# AIM65_FRAM.net
KiCad netlist of a schematic drawn in EAGLE
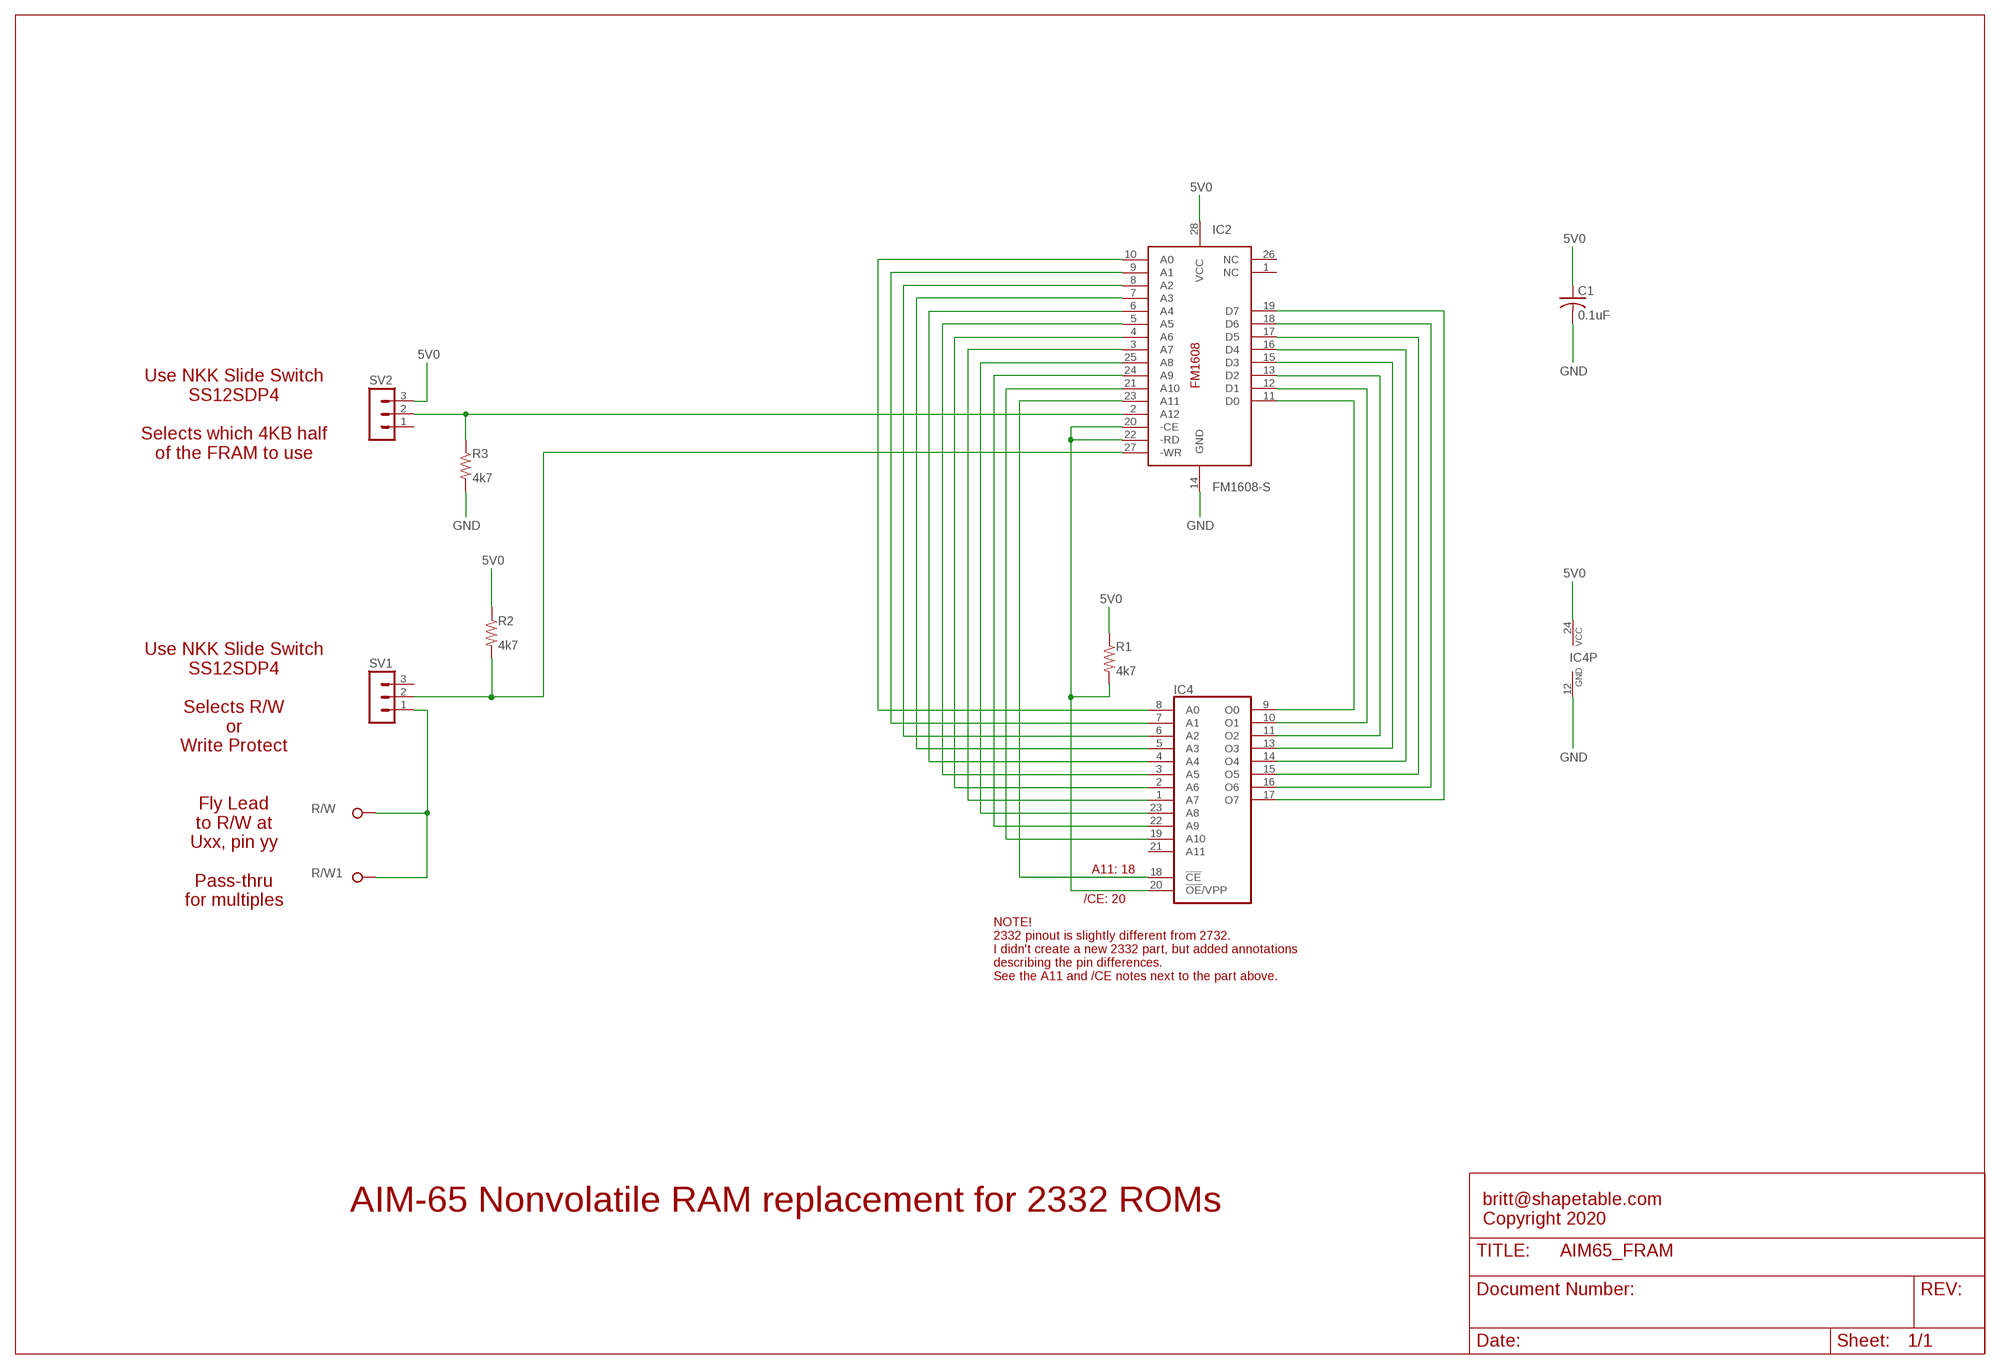
[diagram p0: schematic, sheet 1]

(export (version "E")
  (design (tool "Eeschema 10.0.6"))
  (components
    (comp (ref "C1")
      (value "0.1uF")
      (footprint "eagle-import:C0603K")
      (libsource (lib "eagle-import") (part "C-USC0603K"))
    )
    (comp (ref "IC2")
      (value "FM1608-S")
      (footprint "eagle-import:SO-28W")
      (libsource (lib "eagle-import") (part "FM1608-S"))
    )
    (comp (ref "IC4")
      (value "2732")
      (footprint "eagle-import:DIL24")
      (libsource (lib "eagle-import") (part "2732"))
    )
    (comp (ref "R/W")
      (value "JOE-TP-BIG")
      (footprint "eagle-import:JOE-TP-PKG-BIG")
      (libsource (lib "eagle-import") (part "JOE-TP-BIG"))
    )
    (comp (ref "R/W1")
      (value "JOE-TP-BIG")
      (footprint "eagle-import:JOE-TP-PKG-BIG")
      (libsource (lib "eagle-import") (part "JOE-TP-BIG"))
    )
    (comp (ref "R1")
      (value "4k7")
      (footprint "eagle-import:R0603")
      (libsource (lib "eagle-import") (part "R-US_R0603"))
    )
    (comp (ref "R2")
      (value "4k7")
      (footprint "eagle-import:R0603")
      (libsource (lib "eagle-import") (part "R-US_R0603"))
    )
    (comp (ref "R3")
      (value "4k7")
      (footprint "eagle-import:R0603")
      (libsource (lib "eagle-import") (part "R-US_R0603"))
    )
    (comp (ref "SV1")
      (value "MA03-1")
      (footprint "eagle-import:MA03-1")
      (libsource (lib "eagle-import") (part "MA03-1"))
    )
    (comp (ref "SV2")
      (value "MA03-1")
      (footprint "eagle-import:MA03-1")
      (libsource (lib "eagle-import") (part "MA03-1"))
    )
  )
  (nets
    (net (code "1") (name "/5V0") (class "Default")
      (node (ref "C1") (pin "1") (pinfunction "1_1") (pintype "passive"))
      (node (ref "IC2") (pin "28") (pinfunction "VCC_28") (pintype "power_in"))
      (node (ref "IC4") (pin "24") (pinfunction "VCC_24") (pintype "power_in"))
      (node (ref "R1") (pin "1") (pinfunction "1_1") (pintype "passive"))
      (node (ref "R2") (pin "1") (pinfunction "1_1") (pintype "passive"))
      (node (ref "SV2") (pin "3") (pinfunction "3_3") (pintype "passive"))
    )
    (net (code "2") (name "/GND") (class "Default")
      (node (ref "C1") (pin "2") (pinfunction "2_2") (pintype "passive"))
      (node (ref "IC2") (pin "14") (pinfunction "GND_14") (pintype "power_in"))
      (node (ref "IC4") (pin "12") (pinfunction "GND_12") (pintype "power_in"))
      (node (ref "R3") (pin "2") (pinfunction "2_2") (pintype "passive"))
    )
    (net (code "3") (name "Net-(IC2--CE)") (class "Default")
      (node (ref "IC2") (pin "20") (pinfunction "-CE_20") (pintype "input"))
      (node (ref "IC2") (pin "22") (pinfunction "-RD_22") (pintype "input"))
      (node (ref "IC4") (pin "20") (pinfunction "~{OE}/VPP_20") (pintype "input"))
      (node (ref "R1") (pin "2") (pinfunction "2_2") (pintype "passive"))
    )
    (net (code "4") (name "Net-(IC2--WR)") (class "Default")
      (node (ref "IC2") (pin "27") (pinfunction "-WR_27") (pintype "input"))
      (node (ref "R2") (pin "2") (pinfunction "2_2") (pintype "passive"))
      (node (ref "SV1") (pin "2") (pinfunction "2_2") (pintype "passive"))
    )
    (net (code "5") (name "Net-(IC2-A0)") (class "Default")
      (node (ref "IC2") (pin "10") (pinfunction "A0_10") (pintype "input"))
      (node (ref "IC4") (pin "8") (pinfunction "A0_8") (pintype "input"))
    )
    (net (code "6") (name "Net-(IC2-A1)") (class "Default")
      (node (ref "IC2") (pin "9") (pinfunction "A1_9") (pintype "input"))
      (node (ref "IC4") (pin "7") (pinfunction "A1_7") (pintype "input"))
    )
    (net (code "7") (name "Net-(IC2-A2)") (class "Default")
      (node (ref "IC2") (pin "8") (pinfunction "A2_8") (pintype "input"))
      (node (ref "IC4") (pin "6") (pinfunction "A2_6") (pintype "input"))
    )
    (net (code "8") (name "Net-(IC2-A3)") (class "Default")
      (node (ref "IC2") (pin "7") (pinfunction "A3_7") (pintype "input"))
      (node (ref "IC4") (pin "5") (pinfunction "A3_5") (pintype "input"))
    )
    (net (code "9") (name "Net-(IC2-A4)") (class "Default")
      (node (ref "IC2") (pin "6") (pinfunction "A4_6") (pintype "input"))
      (node (ref "IC4") (pin "4") (pinfunction "A4_4") (pintype "input"))
    )
    (net (code "10") (name "Net-(IC2-A5)") (class "Default")
      (node (ref "IC2") (pin "5") (pinfunction "A5_5") (pintype "input"))
      (node (ref "IC4") (pin "3") (pinfunction "A5_3") (pintype "input"))
    )
    (net (code "11") (name "Net-(IC2-A6)") (class "Default")
      (node (ref "IC2") (pin "4") (pinfunction "A6_4") (pintype "input"))
      (node (ref "IC4") (pin "2") (pinfunction "A6_2") (pintype "input"))
    )
    (net (code "12") (name "Net-(IC2-A7)") (class "Default")
      (node (ref "IC2") (pin "3") (pinfunction "A7_3") (pintype "input"))
      (node (ref "IC4") (pin "1") (pinfunction "A7_1") (pintype "input"))
    )
    (net (code "13") (name "Net-(IC2-A8)") (class "Default")
      (node (ref "IC2") (pin "25") (pinfunction "A8_25") (pintype "input"))
      (node (ref "IC4") (pin "23") (pinfunction "A8_23") (pintype "input"))
    )
    (net (code "14") (name "Net-(IC2-A9)") (class "Default")
      (node (ref "IC2") (pin "24") (pinfunction "A9_24") (pintype "input"))
      (node (ref "IC4") (pin "22") (pinfunction "A9_22") (pintype "input"))
    )
    (net (code "15") (name "Net-(IC2-A10)") (class "Default")
      (node (ref "IC2") (pin "21") (pinfunction "A10_21") (pintype "input"))
      (node (ref "IC4") (pin "19") (pinfunction "A10_19") (pintype "input"))
    )
    (net (code "16") (name "Net-(IC2-A11)") (class "Default")
      (node (ref "IC2") (pin "23") (pinfunction "A11_23") (pintype "input"))
      (node (ref "IC4") (pin "18") (pinfunction "~{CE}_18") (pintype "input"))
    )
    (net (code "17") (name "Net-(IC2-A12)") (class "Default")
      (node (ref "IC2") (pin "2") (pinfunction "A12_2") (pintype "input"))
      (node (ref "R3") (pin "1") (pinfunction "1_1") (pintype "passive"))
      (node (ref "SV2") (pin "2") (pinfunction "2_2") (pintype "passive"))
    )
    (net (code "18") (name "Net-(IC2-D0)") (class "Default")
      (node (ref "IC2") (pin "11") (pinfunction "D0_11") (pintype "bidirectional"))
      (node (ref "IC4") (pin "9") (pinfunction "O0_9") (pintype "tri_state"))
    )
    (net (code "19") (name "Net-(IC2-D1)") (class "Default")
      (node (ref "IC2") (pin "12") (pinfunction "D1_12") (pintype "bidirectional"))
      (node (ref "IC4") (pin "10") (pinfunction "O1_10") (pintype "tri_state"))
    )
    (net (code "20") (name "Net-(IC2-D2)") (class "Default")
      (node (ref "IC2") (pin "13") (pinfunction "D2_13") (pintype "bidirectional"))
      (node (ref "IC4") (pin "11") (pinfunction "O2_11") (pintype "tri_state"))
    )
    (net (code "21") (name "Net-(IC2-D3)") (class "Default")
      (node (ref "IC2") (pin "15") (pinfunction "D3_15") (pintype "bidirectional"))
      (node (ref "IC4") (pin "13") (pinfunction "O3_13") (pintype "tri_state"))
    )
    (net (code "22") (name "Net-(IC2-D4)") (class "Default")
      (node (ref "IC2") (pin "16") (pinfunction "D4_16") (pintype "bidirectional"))
      (node (ref "IC4") (pin "14") (pinfunction "O4_14") (pintype "tri_state"))
    )
    (net (code "23") (name "Net-(IC2-D5)") (class "Default")
      (node (ref "IC2") (pin "17") (pinfunction "D5_17") (pintype "bidirectional"))
      (node (ref "IC4") (pin "15") (pinfunction "O5_15") (pintype "tri_state"))
    )
    (net (code "24") (name "Net-(IC2-D6)") (class "Default")
      (node (ref "IC2") (pin "18") (pinfunction "D6_18") (pintype "bidirectional"))
      (node (ref "IC4") (pin "16") (pinfunction "O6_16") (pintype "tri_state"))
    )
    (net (code "25") (name "Net-(IC2-D7)") (class "Default")
      (node (ref "IC2") (pin "19") (pinfunction "D7_19") (pintype "bidirectional"))
      (node (ref "IC4") (pin "17") (pinfunction "O7_17") (pintype "tri_state"))
    )
    (net (code "26") (name "Net-(R/W-Pad1)") (class "Default")
      (node (ref "R/W") (pin "1") (pinfunction "1_1") (pintype "passive"))
      (node (ref "R/W1") (pin "1") (pinfunction "1_1") (pintype "passive"))
      (node (ref "SV1") (pin "1") (pinfunction "1_1") (pintype "passive"))
    )
    (net (code "27") (name "unconnected-(IC2-NC-Pad1)") (class "Default")
      (node (ref "IC2") (pin "1") (pinfunction "NC_1") (pintype "passive"))
    )
    (net (code "28") (name "unconnected-(IC2-NC-Pad26)") (class "Default")
      (node (ref "IC2") (pin "26") (pinfunction "NC_26") (pintype "passive"))
    )
    (net (code "29") (name "unconnected-(IC4A-A11-Pad21)") (class "Default")
      (node (ref "IC4") (pin "21") (pinfunction "A11_21") (pintype "input"))
    )
    (net (code "30") (name "unconnected-(SV1-Pad3)") (class "Default")
      (node (ref "SV1") (pin "3") (pinfunction "3_3") (pintype "passive"))
    )
    (net (code "31") (name "unconnected-(SV2-Pad1)") (class "Default")
      (node (ref "SV2") (pin "1") (pinfunction "1_1") (pintype "passive"))
    )
  )
)
